# uUSB_breakout_v3.net
KiCad netlist of a schematic drawn in EAGLE
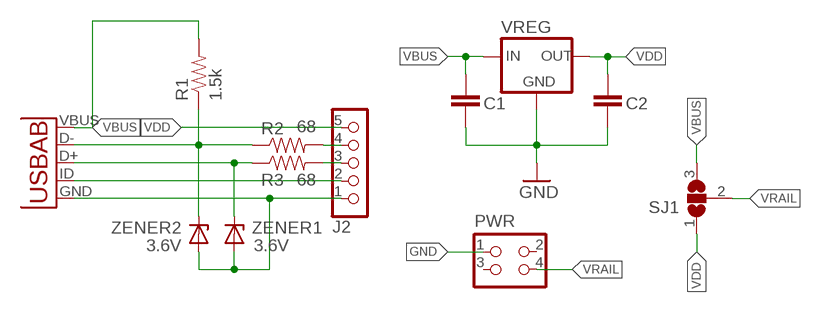
[diagram p0: schematic, sheet 1]

(export (version "E")
  (design (tool "Eeschema 10.0.6"))
  (components
    (comp (ref "C1")
      (value "CAPACITOR_NPOL-0805")
      (footprint "eagle-import:C805")
      (libsource (lib "eagle-import") (part "CAPACITOR_NPOL-0805"))
    )
    (comp (ref "C2")
      (value "CAPACITOR_NPOL-0805")
      (footprint "eagle-import:C805")
      (libsource (lib "eagle-import") (part "CAPACITOR_NPOL-0805"))
    )
    (comp (ref "J2")
      (value "CON_HEADER_1X05-PTH")
      (footprint "eagle-import:M1X5")
      (libsource (lib "eagle-import") (part "CON_HEADER_1X05-PTH"))
    )
    (comp (ref "PWR")
      (value "CON_HEADER_2X02-PTH")
      (footprint "eagle-import:M2X2")
      (libsource (lib "eagle-import") (part "CON_HEADER_2X02-PTH"))
    )
    (comp (ref "R1")
      (value "1.5k")
      (footprint "eagle-import:0805")
      (libsource (lib "eagle-import") (part "RESISTOR0805-RES"))
    )
    (comp (ref "R2")
      (value "68")
      (footprint "eagle-import:0805")
      (libsource (lib "eagle-import") (part "RESISTOR0805-RES"))
    )
    (comp (ref "R3")
      (value "68")
      (footprint "eagle-import:0805")
      (libsource (lib "eagle-import") (part "RESISTOR0805-RES"))
    )
    (comp (ref "SJ1")
      (value "SJ2W")
      (footprint "eagle-import:SJ_2")
      (libsource (lib "eagle-import") (part "SJ2W"))
    )
    (comp (ref "UUSB")
      (value "USB-AB")
      (footprint "eagle-import:USB-AB-MICRO-SMD")
      (libsource (lib "eagle-import") (part "USB-AB"))
    )
    (comp (ref "VREG")
      (value "V_REG_MIC2920")
      (footprint "eagle-import:SOT223")
      (libsource (lib "eagle-import") (part "V_REG_MIC2920"))
    )
    (comp (ref "ZENER1")
      (value "3.6V")
      (footprint "eagle-import:SOD80C")
      (libsource (lib "eagle-import") (part "ZENER-DIODESOD80C"))
    )
    (comp (ref "ZENER2")
      (value "3.6V")
      (footprint "eagle-import:SOD80C")
      (libsource (lib "eagle-import") (part "ZENER-DIODESOD80C"))
    )
  )
  (nets
    (net (code "1") (name "GND") (class "Default")
      (node (ref "C1") (pin "2") (pinfunction "2_2") (pintype "passive"))
      (node (ref "C2") (pin "2") (pinfunction "2_2") (pintype "passive"))
      (node (ref "J2") (pin "1") (pinfunction "1_1") (pintype "bidirectional"))
      (node (ref "PWR") (pin "1") (pinfunction "1_1") (pintype "passive"))
      (node (ref "UUSB") (pin "GND") (pinfunction "GND_GND") (pintype "bidirectional"))
      (node (ref "VREG") (pin "2") (pinfunction "GND_2") (pintype "input"))
      (node (ref "VREG") (pin "4") (pinfunction "GND_4") (pintype "input"))
      (node (ref "ZENER1") (pin "A") (pinfunction "A_A") (pintype "passive"))
      (node (ref "ZENER2") (pin "A") (pinfunction "A_A") (pintype "passive"))
    )
    (net (code "2") (name "Net-(J2-Pad3)") (class "Default")
      (node (ref "J2") (pin "3") (pinfunction "3_3") (pintype "bidirectional"))
      (node (ref "R3") (pin "2") (pinfunction "2_2") (pintype "passive"))
    )
    (net (code "3") (name "Net-(J2-Pad4)") (class "Default")
      (node (ref "J2") (pin "4") (pinfunction "4_4") (pintype "bidirectional"))
      (node (ref "R2") (pin "2") (pinfunction "2_2") (pintype "passive"))
    )
    (net (code "4") (name "Net-(R1-Pad1)") (class "Default")
      (node (ref "R1") (pin "1") (pinfunction "1_1") (pintype "passive"))
      (node (ref "R2") (pin "1") (pinfunction "1_1") (pintype "passive"))
      (node (ref "UUSB") (pin "D-") (pinfunction "D-_D-") (pintype "bidirectional"))
      (node (ref "ZENER2") (pin "C") (pinfunction "C_C") (pintype "passive"))
    )
    (net (code "5") (name "Net-(R3-Pad1)") (class "Default")
      (node (ref "R3") (pin "1") (pinfunction "1_1") (pintype "passive"))
      (node (ref "UUSB") (pin "D+") (pinfunction "D+_D+") (pintype "bidirectional"))
      (node (ref "ZENER1") (pin "C") (pinfunction "C_C") (pintype "passive"))
    )
    (net (code "6") (name "Net-(UUSB-USBID)") (class "Default")
      (node (ref "J2") (pin "2") (pinfunction "2_2") (pintype "bidirectional"))
      (node (ref "UUSB") (pin "ID") (pinfunction "USBID_ID") (pintype "bidirectional"))
    )
    (net (code "7") (name "VBUS") (class "Default")
      (node (ref "C1") (pin "1") (pinfunction "1_1") (pintype "passive"))
      (node (ref "R1") (pin "2") (pinfunction "2_2") (pintype "passive"))
      (node (ref "SJ1") (pin "3") (pinfunction "3_3") (pintype "passive"))
      (node (ref "UUSB") (pin "VBUS") (pinfunction "VBUS_VBUS") (pintype "bidirectional"))
      (node (ref "VREG") (pin "1") (pinfunction "IN_1") (pintype "input"))
    )
    (net (code "8") (name "VDD") (class "Default")
      (node (ref "C2") (pin "1") (pinfunction "1_1") (pintype "passive"))
      (node (ref "J2") (pin "5") (pinfunction "5_5") (pintype "bidirectional"))
      (node (ref "SJ1") (pin "1") (pinfunction "1_1") (pintype "passive"))
      (node (ref "VREG") (pin "3") (pinfunction "OUT_3") (pintype "output"))
    )
    (net (code "9") (name "VRAIL") (class "Default")
      (node (ref "PWR") (pin "4") (pinfunction "4_4") (pintype "passive"))
      (node (ref "SJ1") (pin "2") (pinfunction "2_2") (pintype "passive"))
    )
    (net (code "10") (name "unconnected-(PWR-Pad2)") (class "Default")
      (node (ref "PWR") (pin "2") (pinfunction "2_2") (pintype "passive"))
    )
    (net (code "11") (name "unconnected-(PWR-Pad3)") (class "Default")
      (node (ref "PWR") (pin "3") (pinfunction "3_3") (pintype "passive"))
    )
  )
)
